# tick-mk-4_3.net
KiCad netlist of a schematic drawn in EAGLE
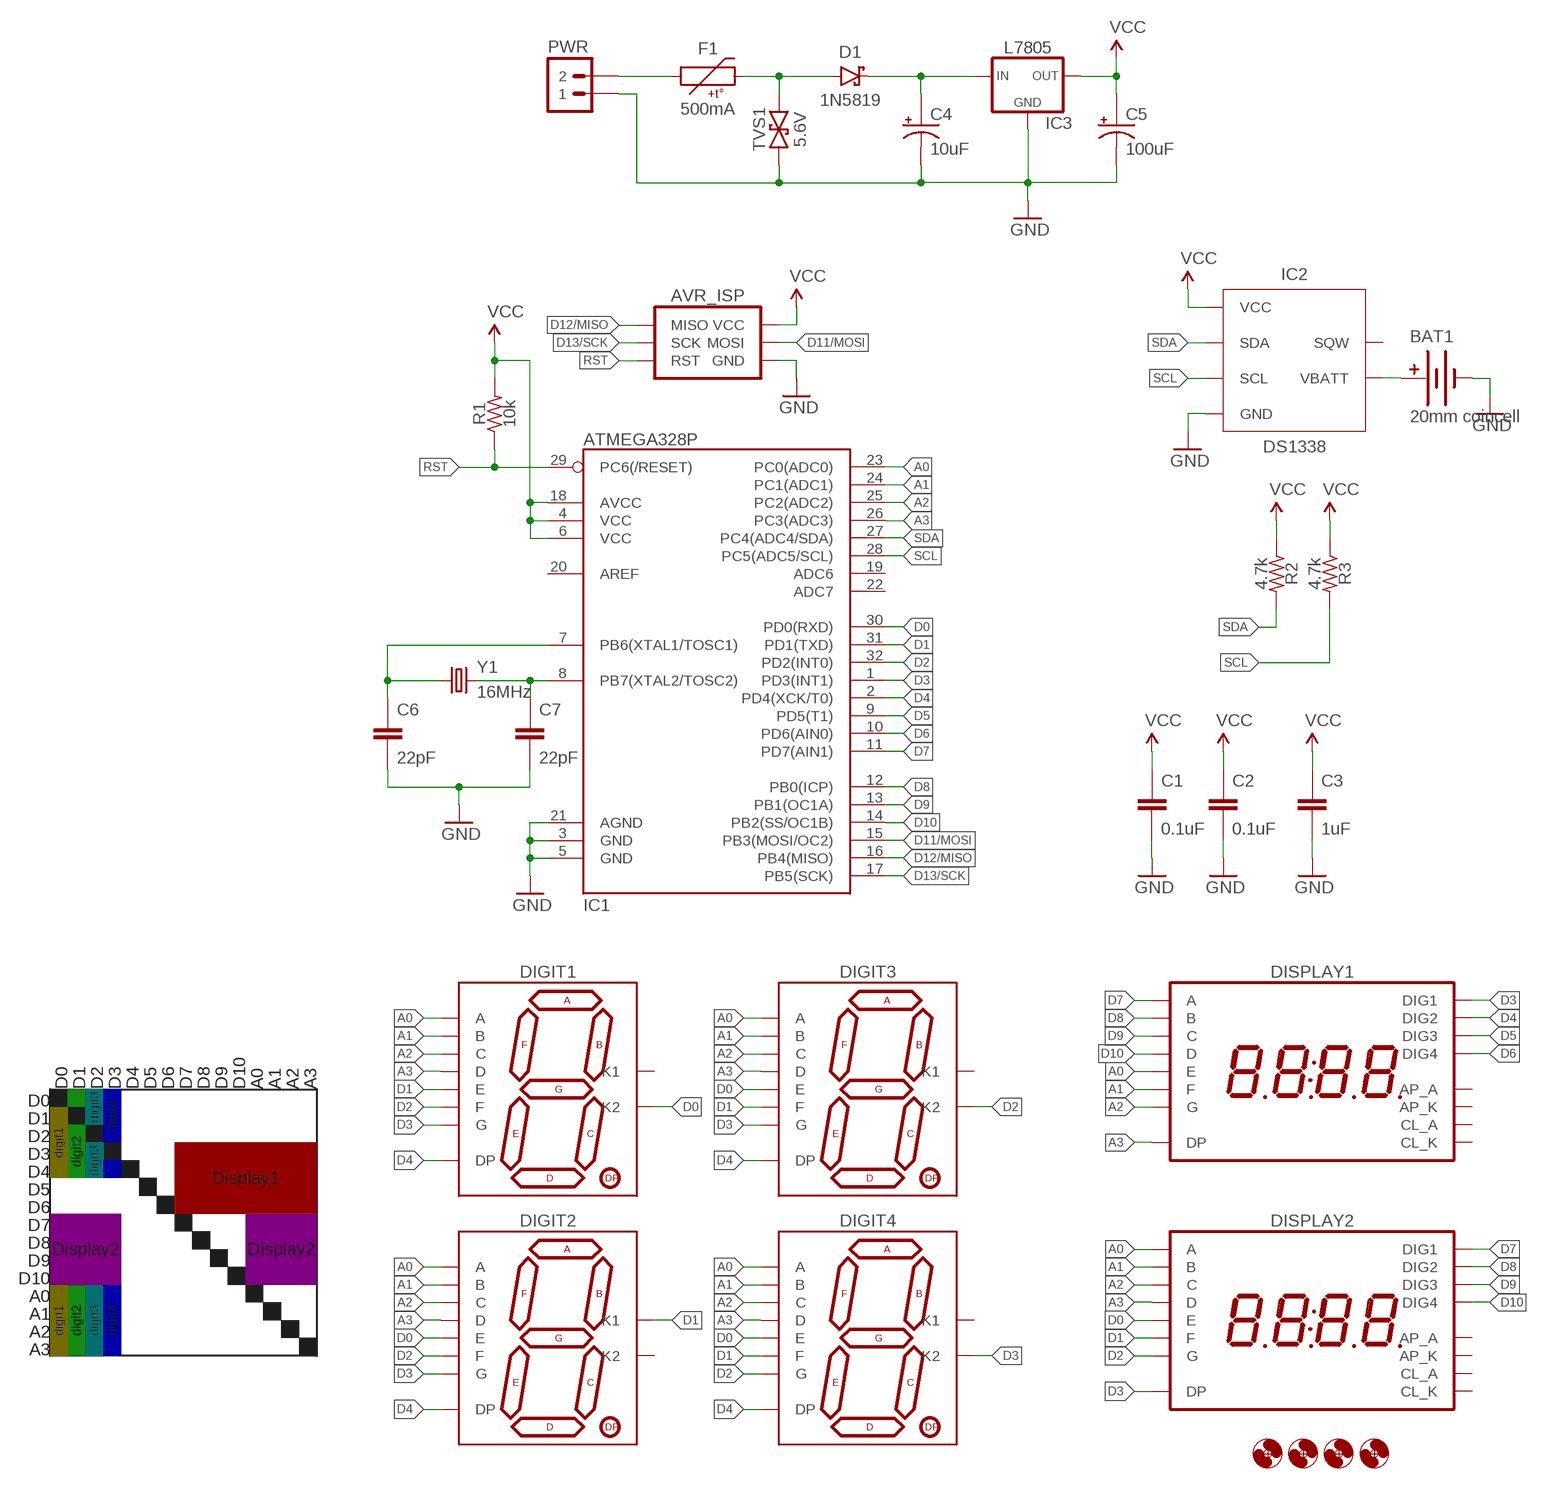
[diagram p0: schematic, sheet 1]

(export (version "E")
  (design (tool "Eeschema 10.0.6"))
  (components
    (comp (ref "AVR_ISP")
      (value "AVR_SPI_PRG_6PTH")
      (footprint "eagle-import:2X3")
      (libsource (lib "eagle-import") (part "AVR_SPI_PRG_6PTH"))
    )
    (comp (ref "BAT1")
      (value "20mm coincell")
      (footprint "eagle-import:BATTCON_20MM_MINE")
      (libsource (lib "eagle-import") (part "BATTERY20MMSMD-MINE"))
    )
    (comp (ref "C1")
      (value "0.1uF")
      (footprint "eagle-import:C025-024X044")
      (libsource (lib "eagle-import") (part "CAPACITOR-CERAMIC025-024X044"))
    )
    (comp (ref "C2")
      (value "0.1uF")
      (footprint "eagle-import:C025-024X044")
      (libsource (lib "eagle-import") (part "CAPACITOR-CERAMIC025-024X044"))
    )
    (comp (ref "C3")
      (value "1uF")
      (footprint "eagle-import:C025-024X044")
      (libsource (lib "eagle-import") (part "CAPACITOR-CERAMIC025-024X044"))
    )
    (comp (ref "C4")
      (value "10uF")
      (footprint "eagle-import:E2-5")
      (libsource (lib "eagle-import") (part "CAPACITOR-POLARIZEDE2-5"))
    )
    (comp (ref "C5")
      (value "100uF")
      (footprint "eagle-import:E2,5-6")
      (libsource (lib "eagle-import") (part "CAPACITOR-POLARIZEDE2.5-6"))
    )
    (comp (ref "C6")
      (value "22pF")
      (footprint "eagle-import:C025-024X044")
      (libsource (lib "eagle-import") (part "CAPACITOR-CERAMIC025-024X044"))
    )
    (comp (ref "C7")
      (value "22pF")
      (footprint "eagle-import:C025-024X044")
      (libsource (lib "eagle-import") (part "CAPACITOR-CERAMIC025-024X044"))
    )
    (comp (ref "D1")
      (value "1N5819")
      (footprint "eagle-import:DIODE-10.16MM")
      (libsource (lib "eagle-import") (part "DIODE-SCHOTTKYPTH-10.16MM"))
    )
    (comp (ref "DIGIT1")
      (value "7SEG_1DIGPTH-25.4MM-BARE")
      (footprint "eagle-import:7SEG_1DIG_25.4MM_NOSILK")
      (libsource (lib "eagle-import") (part "7SEG_1DIGPTH-25.4MM-BARE"))
    )
    (comp (ref "DIGIT2")
      (value "7SEG_1DIGPTH-25.4MM-BARE")
      (footprint "eagle-import:7SEG_1DIG_25.4MM_NOSILK")
      (libsource (lib "eagle-import") (part "7SEG_1DIGPTH-25.4MM-BARE"))
    )
    (comp (ref "DIGIT3")
      (value "7SEG_1DIGPTH-25.4MM-BARE")
      (footprint "eagle-import:7SEG_1DIG_25.4MM_NOSILK")
      (libsource (lib "eagle-import") (part "7SEG_1DIGPTH-25.4MM-BARE"))
    )
    (comp (ref "DIGIT4")
      (value "7SEG_1DIGPTH-25.4MM-BARE")
      (footprint "eagle-import:7SEG_1DIG_25.4MM_NOSILK")
      (libsource (lib "eagle-import") (part "7SEG_1DIGPTH-25.4MM-BARE"))
    )
    (comp (ref "DISPLAY1")
      (value "7SEG_4DIGIT_COLON_APOS")
      (footprint "eagle-import:7SEG_4DIG_10MM")
      (libsource (lib "eagle-import") (part "7SEG_4DIGIT_COLON_APOS"))
    )
    (comp (ref "DISPLAY2")
      (value "7SEG_4DIGIT_COLON_APOS")
      (footprint "eagle-import:7SEG_4DIG_10MM")
      (libsource (lib "eagle-import") (part "7SEG_4DIGIT_COLON_APOS"))
    )
    (comp (ref "F1")
      (value "500mA")
      (footprint "eagle-import:PTC-PTH-5.08MM")
      (libsource (lib "eagle-import") (part "PTCPTH-5.08MM"))
    )
    (comp (ref "H1")
      (value "HOLE#2")
      (footprint "eagle-import:HOLE-#2")
      (libsource (lib "eagle-import") (part "HOLE#2"))
    )
    (comp (ref "H2")
      (value "HOLE#2")
      (footprint "eagle-import:HOLE-#2")
      (libsource (lib "eagle-import") (part "HOLE#2"))
    )
    (comp (ref "H3")
      (value "HOLE#2")
      (footprint "eagle-import:HOLE-#2")
      (libsource (lib "eagle-import") (part "HOLE#2"))
    )
    (comp (ref "H4")
      (value "HOLE#2")
      (footprint "eagle-import:HOLE-#2")
      (libsource (lib "eagle-import") (part "HOLE#2"))
    )
    (comp (ref "IC1")
      (value "ATMEGA328P")
      (footprint "eagle-import:TQFP32-08")
      (libsource (lib "eagle-import") (part "ATMEGA328_SMT"))
    )
    (comp (ref "IC2")
      (value "DS1338")
      (footprint "eagle-import:SO16W")
      (libsource (lib "eagle-import") (part "DS1338CSOIC16W"))
    )
    (comp (ref "IC3")
      (value "L7805")
      (footprint "eagle-import:TO220-IGO-THERMPAD")
      (libsource (lib "eagle-import") (part "V_REG_78XXTO-220-THERMPAD"))
    )
    (comp (ref "PWR")
      (value "M02JST-PTH-VERT")
      (footprint "eagle-import:JST-2-PH-VERT-PTH")
      (libsource (lib "eagle-import") (part "M02JST-PTH-VERT"))
    )
    (comp (ref "R1")
      (value "10k")
      (footprint "eagle-import:RESISTOR-AXIAL-PTH-6.35MM")
      (libsource (lib "eagle-import") (part "RESISTORPTH-AXIAL-6.35MM"))
    )
    (comp (ref "R2")
      (value "4.7k")
      (footprint "eagle-import:RESISTOR-AXIAL-PTH-6.35MM")
      (libsource (lib "eagle-import") (part "RESISTORPTH-AXIAL-6.35MM"))
    )
    (comp (ref "R3")
      (value "4.7k")
      (footprint "eagle-import:RESISTOR-AXIAL-PTH-6.35MM")
      (libsource (lib "eagle-import") (part "RESISTORPTH-AXIAL-6.35MM"))
    )
    (comp (ref "TVS1")
      (value "5.6V")
      (footprint "eagle-import:DO-41-TVS-BI-10.16MM")
      (libsource (lib "eagle-import") (part "TVSDO-41-10.16MM"))
    )
    (comp (ref "Y1")
      (value "16MHz")
      (footprint "eagle-import:HC49U-V")
      (libsource (lib "eagle-import") (part "CRYSTALHC49UV"))
    )
  )
  (nets
    (net (code "1") (name "A0") (class "Default")
      (node (ref "DIGIT1") (pin "7") (pinfunction "A_7") (pintype "bidirectional"))
      (node (ref "DIGIT2") (pin "7") (pinfunction "A_7") (pintype "bidirectional"))
      (node (ref "DIGIT3") (pin "7") (pinfunction "A_7") (pintype "bidirectional"))
      (node (ref "DIGIT4") (pin "7") (pinfunction "A_7") (pintype "bidirectional"))
      (node (ref "DISPLAY1") (pin "5") (pinfunction "E_5") (pintype "passive"))
      (node (ref "DISPLAY2") (pin "14") (pinfunction "A_14") (pintype "passive"))
      (node (ref "IC1") (pin "23") (pinfunction "PC0(ADC0)_23") (pintype "bidirectional"))
    )
    (net (code "2") (name "A1") (class "Default")
      (node (ref "DIGIT1") (pin "6") (pinfunction "B_6") (pintype "bidirectional"))
      (node (ref "DIGIT2") (pin "6") (pinfunction "B_6") (pintype "bidirectional"))
      (node (ref "DIGIT3") (pin "6") (pinfunction "B_6") (pintype "bidirectional"))
      (node (ref "DIGIT4") (pin "6") (pinfunction "B_6") (pintype "bidirectional"))
      (node (ref "DISPLAY1") (pin "11") (pinfunction "F_11") (pintype "passive"))
      (node (ref "DISPLAY2") (pin "16") (pinfunction "B_16") (pintype "passive"))
      (node (ref "IC1") (pin "24") (pinfunction "PC1(ADC1)_24") (pintype "bidirectional"))
    )
    (net (code "3") (name "A2") (class "Default")
      (node (ref "DIGIT1") (pin "4") (pinfunction "C_4") (pintype "bidirectional"))
      (node (ref "DIGIT2") (pin "4") (pinfunction "C_4") (pintype "bidirectional"))
      (node (ref "DIGIT3") (pin "4") (pinfunction "C_4") (pintype "bidirectional"))
      (node (ref "DIGIT4") (pin "4") (pinfunction "C_4") (pintype "bidirectional"))
      (node (ref "DISPLAY1") (pin "15") (pinfunction "G_15") (pintype "passive"))
      (node (ref "DISPLAY2") (pin "13") (pinfunction "C_13") (pintype "passive"))
      (node (ref "IC1") (pin "25") (pinfunction "PC2(ADC2)_25") (pintype "bidirectional"))
    )
    (net (code "4") (name "A3") (class "Default")
      (node (ref "DIGIT1") (pin "2") (pinfunction "D_2") (pintype "bidirectional"))
      (node (ref "DIGIT2") (pin "2") (pinfunction "D_2") (pintype "bidirectional"))
      (node (ref "DIGIT3") (pin "2") (pinfunction "D_2") (pintype "bidirectional"))
      (node (ref "DIGIT4") (pin "2") (pinfunction "D_2") (pintype "bidirectional"))
      (node (ref "DISPLAY1") (pin "7") (pinfunction "DP_7") (pintype "passive"))
      (node (ref "DISPLAY2") (pin "3") (pinfunction "D_3") (pintype "passive"))
      (node (ref "IC1") (pin "26") (pinfunction "PC3(ADC3)_26") (pintype "bidirectional"))
    )
    (net (code "5") (name "D0") (class "Default")
      (node (ref "DIGIT1") (pin "8") (pinfunction "K2_8") (pintype "bidirectional"))
      (node (ref "DIGIT2") (pin "1") (pinfunction "E_1") (pintype "bidirectional"))
      (node (ref "DIGIT3") (pin "1") (pinfunction "E_1") (pintype "bidirectional"))
      (node (ref "DIGIT4") (pin "1") (pinfunction "E_1") (pintype "bidirectional"))
      (node (ref "DISPLAY2") (pin "5") (pinfunction "E_5") (pintype "passive"))
      (node (ref "IC1") (pin "30") (pinfunction "PD0(RXD)_30") (pintype "bidirectional"))
    )
    (net (code "6") (name "D1") (class "Default")
      (node (ref "DIGIT1") (pin "1") (pinfunction "E_1") (pintype "bidirectional"))
      (node (ref "DIGIT2") (pin "3") (pinfunction "K1_3") (pintype "bidirectional"))
      (node (ref "DIGIT3") (pin "9") (pinfunction "F_9") (pintype "bidirectional"))
      (node (ref "DIGIT4") (pin "9") (pinfunction "F_9") (pintype "bidirectional"))
      (node (ref "DISPLAY2") (pin "11") (pinfunction "F_11") (pintype "passive"))
      (node (ref "IC1") (pin "31") (pinfunction "PD1(TXD)_31") (pintype "bidirectional"))
    )
    (net (code "7") (name "D2") (class "Default")
      (node (ref "DIGIT1") (pin "9") (pinfunction "F_9") (pintype "bidirectional"))
      (node (ref "DIGIT2") (pin "9") (pinfunction "F_9") (pintype "bidirectional"))
      (node (ref "DIGIT3") (pin "8") (pinfunction "K2_8") (pintype "bidirectional"))
      (node (ref "DIGIT4") (pin "10") (pinfunction "G_10") (pintype "bidirectional"))
      (node (ref "DISPLAY2") (pin "15") (pinfunction "G_15") (pintype "passive"))
      (node (ref "IC1") (pin "32") (pinfunction "PD2(INT0)_32") (pintype "bidirectional"))
    )
    (net (code "8") (name "D3") (class "Default")
      (node (ref "DIGIT1") (pin "10") (pinfunction "G_10") (pintype "bidirectional"))
      (node (ref "DIGIT2") (pin "10") (pinfunction "G_10") (pintype "bidirectional"))
      (node (ref "DIGIT3") (pin "10") (pinfunction "G_10") (pintype "bidirectional"))
      (node (ref "DIGIT4") (pin "8") (pinfunction "K2_8") (pintype "bidirectional"))
      (node (ref "DISPLAY1") (pin "1") (pinfunction "DIG1_1") (pintype "passive"))
      (node (ref "DISPLAY2") (pin "7") (pinfunction "DP_7") (pintype "passive"))
      (node (ref "IC1") (pin "1") (pinfunction "PD3(INT1)_1") (pintype "bidirectional"))
    )
    (net (code "9") (name "D4") (class "Default")
      (node (ref "DIGIT1") (pin "5") (pinfunction "DP_5") (pintype "bidirectional"))
      (node (ref "DIGIT2") (pin "5") (pinfunction "DP_5") (pintype "bidirectional"))
      (node (ref "DIGIT3") (pin "5") (pinfunction "DP_5") (pintype "bidirectional"))
      (node (ref "DIGIT4") (pin "5") (pinfunction "DP_5") (pintype "bidirectional"))
      (node (ref "DISPLAY1") (pin "2") (pinfunction "DIG2_2") (pintype "passive"))
      (node (ref "IC1") (pin "2") (pinfunction "PD4(XCK/T0)_2") (pintype "bidirectional"))
    )
    (net (code "10") (name "D5") (class "Default")
      (node (ref "DISPLAY1") (pin "6") (pinfunction "DIG3_6") (pintype "passive"))
      (node (ref "IC1") (pin "9") (pinfunction "PD5(T1)_9") (pintype "bidirectional"))
    )
    (net (code "11") (name "D6") (class "Default")
      (node (ref "DISPLAY1") (pin "8") (pinfunction "DIG4_8") (pintype "passive"))
      (node (ref "IC1") (pin "10") (pinfunction "PD6(AIN0)_10") (pintype "bidirectional"))
    )
    (net (code "12") (name "D7") (class "Default")
      (node (ref "DISPLAY1") (pin "14") (pinfunction "A_14") (pintype "passive"))
      (node (ref "DISPLAY2") (pin "1") (pinfunction "DIG1_1") (pintype "passive"))
      (node (ref "IC1") (pin "11") (pinfunction "PD7(AIN1)_11") (pintype "bidirectional"))
    )
    (net (code "13") (name "D8") (class "Default")
      (node (ref "DISPLAY1") (pin "16") (pinfunction "B_16") (pintype "passive"))
      (node (ref "DISPLAY2") (pin "2") (pinfunction "DIG2_2") (pintype "passive"))
      (node (ref "IC1") (pin "12") (pinfunction "PB0(ICP)_12") (pintype "bidirectional"))
    )
    (net (code "14") (name "D9") (class "Default")
      (node (ref "DISPLAY1") (pin "13") (pinfunction "C_13") (pintype "passive"))
      (node (ref "DISPLAY2") (pin "6") (pinfunction "DIG3_6") (pintype "passive"))
      (node (ref "IC1") (pin "13") (pinfunction "PB1(OC1A)_13") (pintype "bidirectional"))
    )
    (net (code "15") (name "D10") (class "Default")
      (node (ref "DISPLAY1") (pin "3") (pinfunction "D_3") (pintype "passive"))
      (node (ref "DISPLAY2") (pin "8") (pinfunction "DIG4_8") (pintype "passive"))
      (node (ref "IC1") (pin "14") (pinfunction "PB2(SS/OC1B)_14") (pintype "bidirectional"))
    )
    (net (code "16") (name "D11{slash}MOSI") (class "Default")
      (node (ref "AVR_ISP") (pin "4") (pinfunction "MOSI_4") (pintype "passive"))
      (node (ref "IC1") (pin "15") (pinfunction "PB3(MOSI/OC2)_15") (pintype "bidirectional"))
    )
    (net (code "17") (name "D12{slash}MISO") (class "Default")
      (node (ref "AVR_ISP") (pin "1") (pinfunction "MISO_1") (pintype "passive"))
      (node (ref "IC1") (pin "16") (pinfunction "PB4(MISO)_16") (pintype "bidirectional"))
    )
    (net (code "18") (name "D13{slash}SCK") (class "Default")
      (node (ref "AVR_ISP") (pin "3") (pinfunction "SCK_3") (pintype "passive"))
      (node (ref "IC1") (pin "17") (pinfunction "PB5(SCK)_17") (pintype "bidirectional"))
    )
    (net (code "19") (name "GND") (class "Default")
      (node (ref "AVR_ISP") (pin "6") (pinfunction "GND_6") (pintype "passive"))
      (node (ref "BAT1") (pin "BOTTOM") (pinfunction "-_BOTTOM") (pintype "power_in"))
      (node (ref "C1") (pin "2") (pinfunction "2_2") (pintype "passive"))
      (node (ref "C2") (pin "2") (pinfunction "2_2") (pintype "passive"))
      (node (ref "C3") (pin "2") (pinfunction "2_2") (pintype "passive"))
      (node (ref "C4") (pin "-") (pinfunction "-_-") (pintype "passive"))
      (node (ref "C5") (pin "-") (pinfunction "-_-") (pintype "passive"))
      (node (ref "C6") (pin "2") (pinfunction "2_2") (pintype "passive"))
      (node (ref "C7") (pin "2") (pinfunction "2_2") (pintype "passive"))
      (node (ref "IC1") (pin "21") (pinfunction "AGND_21") (pintype "bidirectional"))
      (node (ref "IC1") (pin "3") (pinfunction "GND_3") (pintype "bidirectional"))
      (node (ref "IC1") (pin "5") (pinfunction "GND_5") (pintype "bidirectional"))
      (node (ref "IC2") (pin "10") (pinfunction "GND_10") (pintype "bidirectional"))
      (node (ref "IC2") (pin "11") (pinfunction "GND_11") (pintype "bidirectional"))
      (node (ref "IC2") (pin "12") (pinfunction "GND_12") (pintype "bidirectional"))
      (node (ref "IC2") (pin "13") (pinfunction "GND_13") (pintype "bidirectional"))
      (node (ref "IC2") (pin "15") (pinfunction "GND_15") (pintype "bidirectional"))
      (node (ref "IC2") (pin "4") (pinfunction "GND_4") (pintype "bidirectional"))
      (node (ref "IC2") (pin "5") (pinfunction "GND_5") (pintype "bidirectional"))
      (node (ref "IC2") (pin "6") (pinfunction "GND_6") (pintype "bidirectional"))
      (node (ref "IC2") (pin "7") (pinfunction "GND_7") (pintype "bidirectional"))
      (node (ref "IC2") (pin "8") (pinfunction "GND_8") (pintype "bidirectional"))
      (node (ref "IC2") (pin "9") (pinfunction "GND_9") (pintype "bidirectional"))
      (node (ref "IC3") (pin "4") (pinfunction "GND_4") (pintype "bidirectional"))
      (node (ref "IC3") (pin "GND") (pinfunction "GND_GND") (pintype "bidirectional"))
      (node (ref "PWR") (pin "1") (pinfunction "1_1") (pintype "passive"))
      (node (ref "TVS1") (pin "P$1") (pinfunction "1_P$1") (pintype "passive"))
    )
    (net (code "20") (name "Net-(C4-Pad+)") (class "Default")
      (node (ref "C4") (pin "+") (pinfunction "+_+") (pintype "passive"))
      (node (ref "D1") (pin "C") (pinfunction "C_C") (pintype "passive"))
      (node (ref "IC3") (pin "IN") (pinfunction "IN_IN") (pintype "bidirectional"))
    )
    (net (code "21") (name "Net-(F1-1)") (class "Default")
      (node (ref "F1") (pin "P$1") (pinfunction "1_P$1") (pintype "passive"))
      (node (ref "PWR") (pin "2") (pinfunction "2_2") (pintype "passive"))
    )
    (net (code "22") (name "Net-(F1-2)") (class "Default")
      (node (ref "D1") (pin "A") (pinfunction "A_A") (pintype "passive"))
      (node (ref "F1") (pin "P$2") (pinfunction "2_P$2") (pintype "passive"))
      (node (ref "TVS1") (pin "P$2") (pinfunction "2_P$2") (pintype "passive"))
    )
    (net (code "23") (name "Net-(IC1-PB6(XTAL1{slash}TOSC1))") (class "Default")
      (node (ref "C6") (pin "1") (pinfunction "1_1") (pintype "passive"))
      (node (ref "IC1") (pin "7") (pinfunction "PB6(XTAL1/TOSC1)_7") (pintype "bidirectional"))
      (node (ref "Y1") (pin "1") (pinfunction "1_1") (pintype "passive"))
    )
    (net (code "24") (name "Net-(IC1-PB7(XTAL2{slash}TOSC2))") (class "Default")
      (node (ref "C7") (pin "1") (pinfunction "1_1") (pintype "passive"))
      (node (ref "IC1") (pin "8") (pinfunction "PB7(XTAL2/TOSC2)_8") (pintype "bidirectional"))
      (node (ref "Y1") (pin "2") (pinfunction "2_2") (pintype "passive"))
    )
    (net (code "25") (name "Net-(IC2-VBATT)") (class "Default")
      (node (ref "BAT1") (pin "TOP@1") (pinfunction "+_TOP@1") (pintype "power_in"))
      (node (ref "BAT1") (pin "TOP@2") (pinfunction "+_TOP@2") (pintype "power_in"))
      (node (ref "IC2") (pin "14") (pinfunction "VBATT_14") (pintype "bidirectional"))
    )
    (net (code "26") (name "RST") (class "Default")
      (node (ref "AVR_ISP") (pin "5") (pinfunction "RST_5") (pintype "passive"))
      (node (ref "IC1") (pin "29") (pinfunction "PC6(/RESET)_29") (pintype "bidirectional"))
      (node (ref "R1") (pin "P$1") (pinfunction "1_P$1") (pintype "passive"))
    )
    (net (code "27") (name "SCL") (class "Default")
      (node (ref "IC1") (pin "28") (pinfunction "PC5(ADC5/SCL)_28") (pintype "bidirectional"))
      (node (ref "IC2") (pin "1") (pinfunction "SCL_1") (pintype "bidirectional"))
      (node (ref "R3") (pin "P$2") (pinfunction "2_P$2") (pintype "passive"))
    )
    (net (code "28") (name "SDA") (class "Default")
      (node (ref "IC1") (pin "27") (pinfunction "PC4(ADC4/SDA)_27") (pintype "bidirectional"))
      (node (ref "IC2") (pin "16") (pinfunction "SDA_16") (pintype "bidirectional"))
      (node (ref "R2") (pin "P$2") (pinfunction "2_P$2") (pintype "passive"))
    )
    (net (code "29") (name "VCC") (class "Default")
      (node (ref "AVR_ISP") (pin "2") (pinfunction "VCC_2") (pintype "passive"))
      (node (ref "C1") (pin "1") (pinfunction "1_1") (pintype "passive"))
      (node (ref "C2") (pin "1") (pinfunction "1_1") (pintype "passive"))
      (node (ref "C3") (pin "1") (pinfunction "1_1") (pintype "passive"))
      (node (ref "C5") (pin "+") (pinfunction "+_+") (pintype "passive"))
      (node (ref "IC1") (pin "18") (pinfunction "AVCC_18") (pintype "bidirectional"))
      (node (ref "IC1") (pin "4") (pinfunction "VCC_4") (pintype "bidirectional"))
      (node (ref "IC1") (pin "6") (pinfunction "VCC_6") (pintype "bidirectional"))
      (node (ref "IC2") (pin "3") (pinfunction "VCC_3") (pintype "bidirectional"))
      (node (ref "IC3") (pin "OUT") (pinfunction "OUT_OUT") (pintype "bidirectional"))
      (node (ref "R1") (pin "P$2") (pinfunction "2_P$2") (pintype "passive"))
      (node (ref "R2") (pin "P$1") (pinfunction "1_P$1") (pintype "passive"))
      (node (ref "R3") (pin "P$1") (pinfunction "1_P$1") (pintype "passive"))
    )
    (net (code "30") (name "unconnected-(DIGIT1-K1-Pad3)") (class "Default")
      (node (ref "DIGIT1") (pin "3") (pinfunction "K1_3") (pintype "bidirectional"))
    )
    (net (code "31") (name "unconnected-(DIGIT2-K2-Pad8)") (class "Default")
      (node (ref "DIGIT2") (pin "8") (pinfunction "K2_8") (pintype "bidirectional"))
    )
    (net (code "32") (name "unconnected-(DIGIT3-K1-Pad3)") (class "Default")
      (node (ref "DIGIT3") (pin "3") (pinfunction "K1_3") (pintype "bidirectional"))
    )
    (net (code "33") (name "unconnected-(DIGIT4-K1-Pad3)") (class "Default")
      (node (ref "DIGIT4") (pin "3") (pinfunction "K1_3") (pintype "bidirectional"))
    )
    (net (code "34") (name "unconnected-(DISPLAY1-AP_A-Pad10)") (class "Default")
      (node (ref "DISPLAY1") (pin "10") (pinfunction "AP_A_10") (pintype "bidirectional"))
    )
    (net (code "35") (name "unconnected-(DISPLAY1-AP_K-Pad9)") (class "Default")
      (node (ref "DISPLAY1") (pin "9") (pinfunction "AP_K_9") (pintype "bidirectional"))
    )
    (net (code "36") (name "unconnected-(DISPLAY1-CL_A-Pad4)") (class "Default")
      (node (ref "DISPLAY1") (pin "4") (pinfunction "CL_A_4") (pintype "passive"))
    )
    (net (code "37") (name "unconnected-(DISPLAY1-CL_K-Pad12)") (class "Default")
      (node (ref "DISPLAY1") (pin "12") (pinfunction "CL_K_12") (pintype "passive"))
    )
    (net (code "38") (name "unconnected-(DISPLAY2-AP_A-Pad10)") (class "Default")
      (node (ref "DISPLAY2") (pin "10") (pinfunction "AP_A_10") (pintype "bidirectional"))
    )
    (net (code "39") (name "unconnected-(DISPLAY2-AP_K-Pad9)") (class "Default")
      (node (ref "DISPLAY2") (pin "9") (pinfunction "AP_K_9") (pintype "bidirectional"))
    )
    (net (code "40") (name "unconnected-(DISPLAY2-CL_A-Pad4)") (class "Default")
      (node (ref "DISPLAY2") (pin "4") (pinfunction "CL_A_4") (pintype "passive"))
    )
    (net (code "41") (name "unconnected-(DISPLAY2-CL_K-Pad12)") (class "Default")
      (node (ref "DISPLAY2") (pin "12") (pinfunction "CL_K_12") (pintype "passive"))
    )
    (net (code "42") (name "unconnected-(IC1-ADC6-Pad19)") (class "Default")
      (node (ref "IC1") (pin "19") (pinfunction "ADC6_19") (pintype "bidirectional"))
    )
    (net (code "43") (name "unconnected-(IC1-ADC7-Pad22)") (class "Default")
      (node (ref "IC1") (pin "22") (pinfunction "ADC7_22") (pintype "bidirectional"))
    )
    (net (code "44") (name "unconnected-(IC1-AREF-Pad20)") (class "Default")
      (node (ref "IC1") (pin "20") (pinfunction "AREF_20") (pintype "bidirectional"))
    )
    (net (code "45") (name "unconnected-(IC2-SQW-Pad2)") (class "Default")
      (node (ref "IC2") (pin "2") (pinfunction "SQW_2") (pintype "bidirectional"))
    )
  )
)
